# signal-board_v1_21.net
KiCad netlist of a schematic drawn in EAGLE
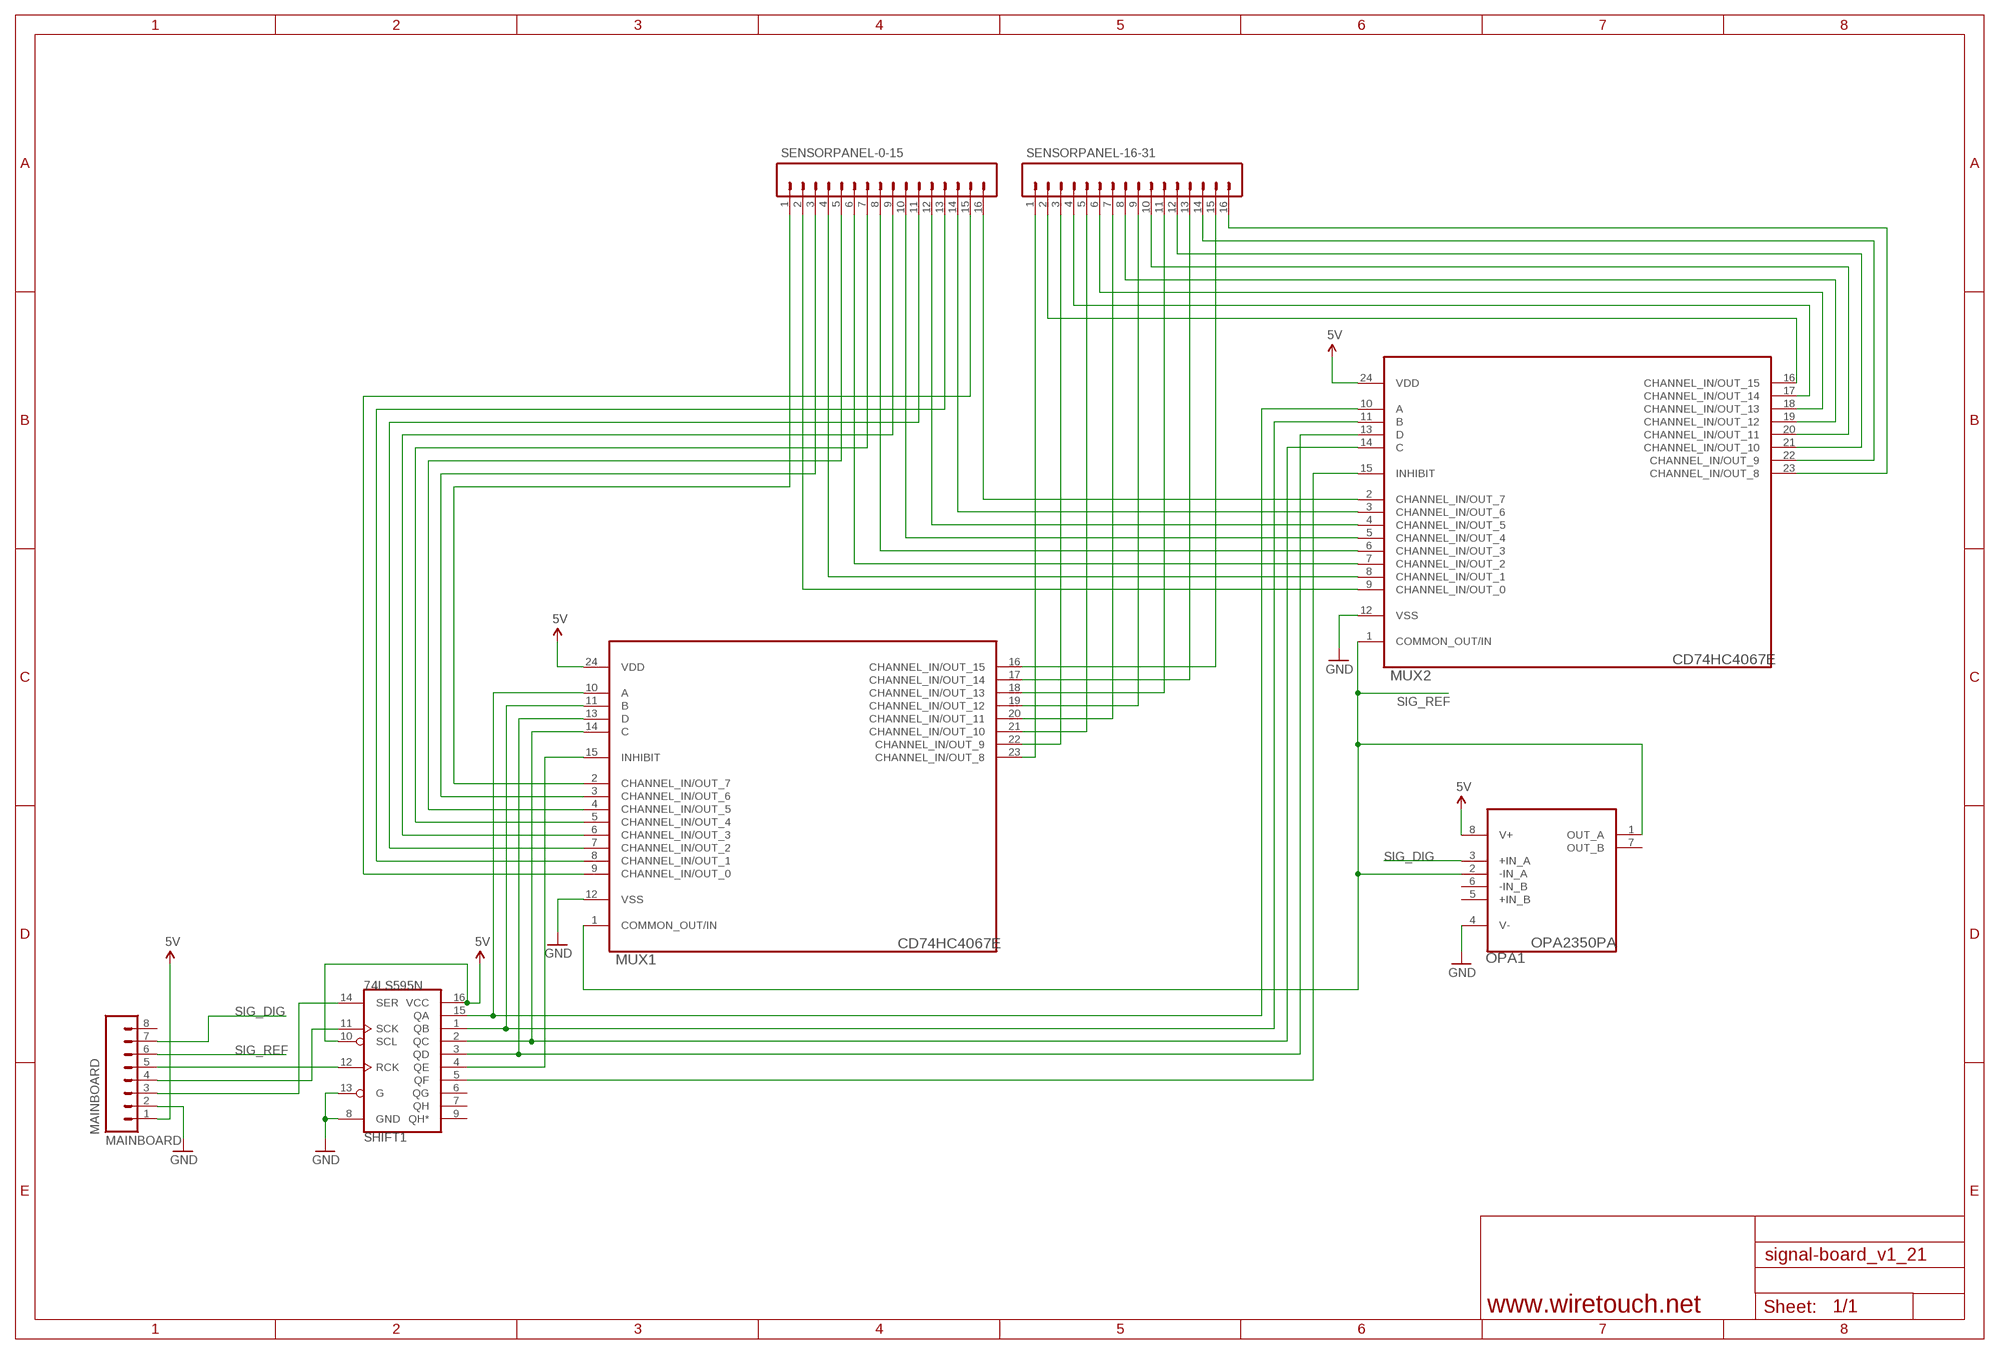
[diagram p0: schematic, sheet 1]

(export (version "E")
  (design (tool "Eeschema 10.0.6"))
  (components
    (comp (ref "MAINBOARD")
      (value "MAINBOARD")
      (footprint "eagle-import:1X08_LONGPADS")
      (libsource (lib "eagle-import") (part "M08LONGPADS"))
    )
    (comp (ref "MUX1")
      (value "CD74HC4067E")
      (footprint "eagle-import:PDIP24-WIDE-CD74HC4067E")
      (libsource (lib "eagle-import") (part "CD74HC4067E"))
    )
    (comp (ref "MUX2")
      (value "CD74HC4067E")
      (footprint "eagle-import:PDIP24-WIDE-CD74HC4067E")
      (libsource (lib "eagle-import") (part "CD74HC4067E"))
    )
    (comp (ref "OPA1")
      (value "OPA2350PA")
      (footprint "eagle-import:DIP254P762X508-8")
      (libsource (lib "eagle-import") (part "OPA2350PA"))
    )
    (comp (ref "SENSORPANEL-0-15")
      (value "M16LOCK_LONGPADS")
      (footprint "eagle-import:1X16_LOCK_LONGPADS")
      (libsource (lib "eagle-import") (part "M16LOCK_LONGPADS"))
    )
    (comp (ref "SENSORPANEL-16-31")
      (value "M16LOCK_LONGPADS")
      (footprint "eagle-import:1X16_LOCK_LONGPADS")
      (libsource (lib "eagle-import") (part "M16LOCK_LONGPADS"))
    )
    (comp (ref "SHIFT1")
      (value "74LS595N")
      (footprint "eagle-import:DIL16")
      (libsource (lib "eagle-import") (part "74595NLS"))
    )
  )
  (nets
    (net (code "1") (name "/SIG_DIG") (class "Default")
      (node (ref "MAINBOARD") (pin "7") (pinfunction "7_7") (pintype "passive"))
      (node (ref "OPA1") (pin "3") (pinfunction "+IN_A_3") (pintype "input"))
    )
    (net (code "2") (name "/SIG_REF") (class "Default")
      (node (ref "MAINBOARD") (pin "6") (pinfunction "6_6") (pintype "passive"))
      (node (ref "MUX1") (pin "1") (pinfunction "COMMON_OUT/IN_1") (pintype "passive"))
      (node (ref "MUX2") (pin "1") (pinfunction "COMMON_OUT/IN_1") (pintype "passive"))
      (node (ref "OPA1") (pin "1") (pinfunction "OUT_A_1") (pintype "output"))
      (node (ref "OPA1") (pin "2") (pinfunction "-IN_A_2") (pintype "input"))
    )
    (net (code "3") (name "5V") (class "Default")
      (node (ref "MAINBOARD") (pin "1") (pinfunction "1_1") (pintype "passive"))
      (node (ref "MUX1") (pin "24") (pinfunction "VDD_24") (pintype "power_in"))
      (node (ref "MUX2") (pin "24") (pinfunction "VDD_24") (pintype "power_in"))
      (node (ref "OPA1") (pin "8") (pinfunction "V+_8") (pintype "power_in"))
      (node (ref "SHIFT1") (pin "10") (pinfunction "SCL_10") (pintype "input"))
      (node (ref "SHIFT1") (pin "16") (pinfunction "VCC_16") (pintype "power_in"))
    )
    (net (code "4") (name "GND") (class "Default")
      (node (ref "MAINBOARD") (pin "2") (pinfunction "2_2") (pintype "passive"))
      (node (ref "MUX1") (pin "12") (pinfunction "VSS_12") (pintype "power_in"))
      (node (ref "MUX2") (pin "12") (pinfunction "VSS_12") (pintype "power_in"))
      (node (ref "OPA1") (pin "4") (pinfunction "V-_4") (pintype "power_in"))
      (node (ref "SHIFT1") (pin "13") (pinfunction "G_13") (pintype "input"))
      (node (ref "SHIFT1") (pin "8") (pinfunction "GND_8") (pintype "power_in"))
    )
    (net (code "5") (name "Net-(MUX1-A)") (class "Default")
      (node (ref "MUX1") (pin "10") (pinfunction "A_10") (pintype "input"))
      (node (ref "MUX2") (pin "10") (pinfunction "A_10") (pintype "input"))
      (node (ref "SHIFT1") (pin "15") (pinfunction "QA_15") (pintype "tri_state"))
    )
    (net (code "6") (name "Net-(MUX1-B)") (class "Default")
      (node (ref "MUX1") (pin "11") (pinfunction "B_11") (pintype "input"))
      (node (ref "MUX2") (pin "11") (pinfunction "B_11") (pintype "input"))
      (node (ref "SHIFT1") (pin "1") (pinfunction "QB_1") (pintype "tri_state"))
    )
    (net (code "7") (name "Net-(MUX1-C)") (class "Default")
      (node (ref "MUX1") (pin "14") (pinfunction "C_14") (pintype "input"))
      (node (ref "MUX2") (pin "14") (pinfunction "C_14") (pintype "input"))
      (node (ref "SHIFT1") (pin "2") (pinfunction "QC_2") (pintype "tri_state"))
    )
    (net (code "8") (name "Net-(MUX1-CHANNEL_IN{slash}OUT_0)") (class "Default")
      (node (ref "MUX1") (pin "9") (pinfunction "CHANNEL_IN/OUT_0_9") (pintype "bidirectional"))
      (node (ref "SENSORPANEL-0-15") (pin "15") (pinfunction "15_15") (pintype "passive"))
    )
    (net (code "9") (name "Net-(MUX1-CHANNEL_IN{slash}OUT_1)") (class "Default")
      (node (ref "MUX1") (pin "8") (pinfunction "CHANNEL_IN/OUT_1_8") (pintype "bidirectional"))
      (node (ref "SENSORPANEL-0-15") (pin "13") (pinfunction "13_13") (pintype "passive"))
    )
    (net (code "10") (name "Net-(MUX1-CHANNEL_IN{slash}OUT_2)") (class "Default")
      (node (ref "MUX1") (pin "7") (pinfunction "CHANNEL_IN/OUT_2_7") (pintype "bidirectional"))
      (node (ref "SENSORPANEL-0-15") (pin "11") (pinfunction "11_11") (pintype "passive"))
    )
    (net (code "11") (name "Net-(MUX1-CHANNEL_IN{slash}OUT_3)") (class "Default")
      (node (ref "MUX1") (pin "6") (pinfunction "CHANNEL_IN/OUT_3_6") (pintype "bidirectional"))
      (node (ref "SENSORPANEL-0-15") (pin "9") (pinfunction "9_9") (pintype "passive"))
    )
    (net (code "12") (name "Net-(MUX1-CHANNEL_IN{slash}OUT_4)") (class "Default")
      (node (ref "MUX1") (pin "5") (pinfunction "CHANNEL_IN/OUT_4_5") (pintype "bidirectional"))
      (node (ref "SENSORPANEL-0-15") (pin "7") (pinfunction "7_7") (pintype "passive"))
    )
    (net (code "13") (name "Net-(MUX1-CHANNEL_IN{slash}OUT_5)") (class "Default")
      (node (ref "MUX1") (pin "4") (pinfunction "CHANNEL_IN/OUT_5_4") (pintype "bidirectional"))
      (node (ref "SENSORPANEL-0-15") (pin "5") (pinfunction "5_5") (pintype "passive"))
    )
    (net (code "14") (name "Net-(MUX1-CHANNEL_IN{slash}OUT_6)") (class "Default")
      (node (ref "MUX1") (pin "3") (pinfunction "CHANNEL_IN/OUT_6_3") (pintype "bidirectional"))
      (node (ref "SENSORPANEL-0-15") (pin "3") (pinfunction "3_3") (pintype "passive"))
    )
    (net (code "15") (name "Net-(MUX1-CHANNEL_IN{slash}OUT_7)") (class "Default")
      (node (ref "MUX1") (pin "2") (pinfunction "CHANNEL_IN/OUT_7_2") (pintype "bidirectional"))
      (node (ref "SENSORPANEL-0-15") (pin "1") (pinfunction "1_1") (pintype "passive"))
    )
    (net (code "16") (name "Net-(MUX1-CHANNEL_IN{slash}OUT_8)") (class "Default")
      (node (ref "MUX1") (pin "23") (pinfunction "CHANNEL_IN/OUT_8_23") (pintype "bidirectional"))
      (node (ref "SENSORPANEL-16-31") (pin "1") (pinfunction "1_1") (pintype "passive"))
    )
    (net (code "17") (name "Net-(MUX1-CHANNEL_IN{slash}OUT_9)") (class "Default")
      (node (ref "MUX1") (pin "22") (pinfunction "CHANNEL_IN/OUT_9_22") (pintype "bidirectional"))
      (node (ref "SENSORPANEL-16-31") (pin "3") (pinfunction "3_3") (pintype "passive"))
    )
    (net (code "18") (name "Net-(MUX1-CHANNEL_IN{slash}OUT_10)") (class "Default")
      (node (ref "MUX1") (pin "21") (pinfunction "CHANNEL_IN/OUT_10_21") (pintype "bidirectional"))
      (node (ref "SENSORPANEL-16-31") (pin "5") (pinfunction "5_5") (pintype "passive"))
    )
    (net (code "19") (name "Net-(MUX1-CHANNEL_IN{slash}OUT_11)") (class "Default")
      (node (ref "MUX1") (pin "20") (pinfunction "CHANNEL_IN/OUT_11_20") (pintype "bidirectional"))
      (node (ref "SENSORPANEL-16-31") (pin "7") (pinfunction "7_7") (pintype "passive"))
    )
    (net (code "20") (name "Net-(MUX1-CHANNEL_IN{slash}OUT_12)") (class "Default")
      (node (ref "MUX1") (pin "19") (pinfunction "CHANNEL_IN/OUT_12_19") (pintype "bidirectional"))
      (node (ref "SENSORPANEL-16-31") (pin "9") (pinfunction "9_9") (pintype "passive"))
    )
    (net (code "21") (name "Net-(MUX1-CHANNEL_IN{slash}OUT_13)") (class "Default")
      (node (ref "MUX1") (pin "18") (pinfunction "CHANNEL_IN/OUT_13_18") (pintype "bidirectional"))
      (node (ref "SENSORPANEL-16-31") (pin "11") (pinfunction "11_11") (pintype "passive"))
    )
    (net (code "22") (name "Net-(MUX1-CHANNEL_IN{slash}OUT_14)") (class "Default")
      (node (ref "MUX1") (pin "17") (pinfunction "CHANNEL_IN/OUT_14_17") (pintype "bidirectional"))
      (node (ref "SENSORPANEL-16-31") (pin "13") (pinfunction "13_13") (pintype "passive"))
    )
    (net (code "23") (name "Net-(MUX1-CHANNEL_IN{slash}OUT_15)") (class "Default")
      (node (ref "MUX1") (pin "16") (pinfunction "CHANNEL_IN/OUT_15_16") (pintype "bidirectional"))
      (node (ref "SENSORPANEL-16-31") (pin "15") (pinfunction "15_15") (pintype "passive"))
    )
    (net (code "24") (name "Net-(MUX1-D)") (class "Default")
      (node (ref "MUX1") (pin "13") (pinfunction "D_13") (pintype "input"))
      (node (ref "MUX2") (pin "13") (pinfunction "D_13") (pintype "input"))
      (node (ref "SHIFT1") (pin "3") (pinfunction "QD_3") (pintype "tri_state"))
    )
    (net (code "25") (name "Net-(MUX1-INHIBIT)") (class "Default")
      (node (ref "MUX1") (pin "15") (pinfunction "INHIBIT_15") (pintype "input"))
      (node (ref "SHIFT1") (pin "4") (pinfunction "QE_4") (pintype "tri_state"))
    )
    (net (code "26") (name "Net-(MUX2-CHANNEL_IN{slash}OUT_0)") (class "Default")
      (node (ref "MUX2") (pin "9") (pinfunction "CHANNEL_IN/OUT_0_9") (pintype "bidirectional"))
      (node (ref "SENSORPANEL-0-15") (pin "2") (pinfunction "2_2") (pintype "passive"))
    )
    (net (code "27") (name "Net-(MUX2-CHANNEL_IN{slash}OUT_1)") (class "Default")
      (node (ref "MUX2") (pin "8") (pinfunction "CHANNEL_IN/OUT_1_8") (pintype "bidirectional"))
      (node (ref "SENSORPANEL-0-15") (pin "4") (pinfunction "4_4") (pintype "passive"))
    )
    (net (code "28") (name "Net-(MUX2-CHANNEL_IN{slash}OUT_2)") (class "Default")
      (node (ref "MUX2") (pin "7") (pinfunction "CHANNEL_IN/OUT_2_7") (pintype "bidirectional"))
      (node (ref "SENSORPANEL-0-15") (pin "6") (pinfunction "6_6") (pintype "passive"))
    )
    (net (code "29") (name "Net-(MUX2-CHANNEL_IN{slash}OUT_3)") (class "Default")
      (node (ref "MUX2") (pin "6") (pinfunction "CHANNEL_IN/OUT_3_6") (pintype "bidirectional"))
      (node (ref "SENSORPANEL-0-15") (pin "8") (pinfunction "8_8") (pintype "passive"))
    )
    (net (code "30") (name "Net-(MUX2-CHANNEL_IN{slash}OUT_4)") (class "Default")
      (node (ref "MUX2") (pin "5") (pinfunction "CHANNEL_IN/OUT_4_5") (pintype "bidirectional"))
      (node (ref "SENSORPANEL-0-15") (pin "10") (pinfunction "10_10") (pintype "passive"))
    )
    (net (code "31") (name "Net-(MUX2-CHANNEL_IN{slash}OUT_5)") (class "Default")
      (node (ref "MUX2") (pin "4") (pinfunction "CHANNEL_IN/OUT_5_4") (pintype "bidirectional"))
      (node (ref "SENSORPANEL-0-15") (pin "12") (pinfunction "12_12") (pintype "passive"))
    )
    (net (code "32") (name "Net-(MUX2-CHANNEL_IN{slash}OUT_6)") (class "Default")
      (node (ref "MUX2") (pin "3") (pinfunction "CHANNEL_IN/OUT_6_3") (pintype "bidirectional"))
      (node (ref "SENSORPANEL-0-15") (pin "14") (pinfunction "14_14") (pintype "passive"))
    )
    (net (code "33") (name "Net-(MUX2-CHANNEL_IN{slash}OUT_7)") (class "Default")
      (node (ref "MUX2") (pin "2") (pinfunction "CHANNEL_IN/OUT_7_2") (pintype "bidirectional"))
      (node (ref "SENSORPANEL-0-15") (pin "16") (pinfunction "16_16") (pintype "passive"))
    )
    (net (code "34") (name "Net-(MUX2-CHANNEL_IN{slash}OUT_8)") (class "Default")
      (node (ref "MUX2") (pin "23") (pinfunction "CHANNEL_IN/OUT_8_23") (pintype "bidirectional"))
      (node (ref "SENSORPANEL-16-31") (pin "16") (pinfunction "16_16") (pintype "passive"))
    )
    (net (code "35") (name "Net-(MUX2-CHANNEL_IN{slash}OUT_9)") (class "Default")
      (node (ref "MUX2") (pin "22") (pinfunction "CHANNEL_IN/OUT_9_22") (pintype "bidirectional"))
      (node (ref "SENSORPANEL-16-31") (pin "14") (pinfunction "14_14") (pintype "passive"))
    )
    (net (code "36") (name "Net-(MUX2-CHANNEL_IN{slash}OUT_10)") (class "Default")
      (node (ref "MUX2") (pin "21") (pinfunction "CHANNEL_IN/OUT_10_21") (pintype "bidirectional"))
      (node (ref "SENSORPANEL-16-31") (pin "12") (pinfunction "12_12") (pintype "passive"))
    )
    (net (code "37") (name "Net-(MUX2-CHANNEL_IN{slash}OUT_11)") (class "Default")
      (node (ref "MUX2") (pin "20") (pinfunction "CHANNEL_IN/OUT_11_20") (pintype "bidirectional"))
      (node (ref "SENSORPANEL-16-31") (pin "10") (pinfunction "10_10") (pintype "passive"))
    )
    (net (code "38") (name "Net-(MUX2-CHANNEL_IN{slash}OUT_12)") (class "Default")
      (node (ref "MUX2") (pin "19") (pinfunction "CHANNEL_IN/OUT_12_19") (pintype "bidirectional"))
      (node (ref "SENSORPANEL-16-31") (pin "8") (pinfunction "8_8") (pintype "passive"))
    )
    (net (code "39") (name "Net-(MUX2-CHANNEL_IN{slash}OUT_13)") (class "Default")
      (node (ref "MUX2") (pin "18") (pinfunction "CHANNEL_IN/OUT_13_18") (pintype "bidirectional"))
      (node (ref "SENSORPANEL-16-31") (pin "6") (pinfunction "6_6") (pintype "passive"))
    )
    (net (code "40") (name "Net-(MUX2-CHANNEL_IN{slash}OUT_14)") (class "Default")
      (node (ref "MUX2") (pin "17") (pinfunction "CHANNEL_IN/OUT_14_17") (pintype "bidirectional"))
      (node (ref "SENSORPANEL-16-31") (pin "4") (pinfunction "4_4") (pintype "passive"))
    )
    (net (code "41") (name "Net-(MUX2-CHANNEL_IN{slash}OUT_15)") (class "Default")
      (node (ref "MUX2") (pin "16") (pinfunction "CHANNEL_IN/OUT_15_16") (pintype "bidirectional"))
      (node (ref "SENSORPANEL-16-31") (pin "2") (pinfunction "2_2") (pintype "passive"))
    )
    (net (code "42") (name "Net-(MUX2-INHIBIT)") (class "Default")
      (node (ref "MUX2") (pin "15") (pinfunction "INHIBIT_15") (pintype "input"))
      (node (ref "SHIFT1") (pin "5") (pinfunction "QF_5") (pintype "tri_state"))
    )
    (net (code "43") (name "Net-(SHIFT1-RCK)") (class "Default")
      (node (ref "MAINBOARD") (pin "5") (pinfunction "5_5") (pintype "passive"))
      (node (ref "SHIFT1") (pin "12") (pinfunction "RCK_12") (pintype "input"))
    )
    (net (code "44") (name "Net-(SHIFT1-SCK)") (class "Default")
      (node (ref "MAINBOARD") (pin "4") (pinfunction "4_4") (pintype "passive"))
      (node (ref "SHIFT1") (pin "11") (pinfunction "SCK_11") (pintype "input"))
    )
    (net (code "45") (name "Net-(SHIFT1-SER)") (class "Default")
      (node (ref "MAINBOARD") (pin "3") (pinfunction "3_3") (pintype "passive"))
      (node (ref "SHIFT1") (pin "14") (pinfunction "SER_14") (pintype "input"))
    )
    (net (code "46") (name "unconnected-(MAINBOARD-Pad8)") (class "Default")
      (node (ref "MAINBOARD") (pin "8") (pinfunction "8_8") (pintype "passive"))
    )
    (net (code "47") (name "unconnected-(OPA1-+IN_B-Pad5)") (class "Default")
      (node (ref "OPA1") (pin "5") (pinfunction "+IN_B_5") (pintype "input"))
    )
    (net (code "48") (name "unconnected-(OPA1--IN_B-Pad6)") (class "Default")
      (node (ref "OPA1") (pin "6") (pinfunction "-IN_B_6") (pintype "input"))
    )
    (net (code "49") (name "unconnected-(OPA1-OUT_B-Pad7)") (class "Default")
      (node (ref "OPA1") (pin "7") (pinfunction "OUT_B_7") (pintype "output"))
    )
    (net (code "50") (name "unconnected-(SHIFT1-QG-Pad6)") (class "Default")
      (node (ref "SHIFT1") (pin "6") (pinfunction "QG_6") (pintype "tri_state"))
    )
    (net (code "51") (name "unconnected-(SHIFT1-QH*-Pad9)") (class "Default")
      (node (ref "SHIFT1") (pin "9") (pinfunction "QH*_9") (pintype "tri_state"))
    )
    (net (code "52") (name "unconnected-(SHIFT1-QH-Pad7)") (class "Default")
      (node (ref "SHIFT1") (pin "7") (pinfunction "QH_7") (pintype "tri_state"))
    )
  )
)
